# BMS-FETs.net
KiCad netlist of a schematic drawn in Altium Designer
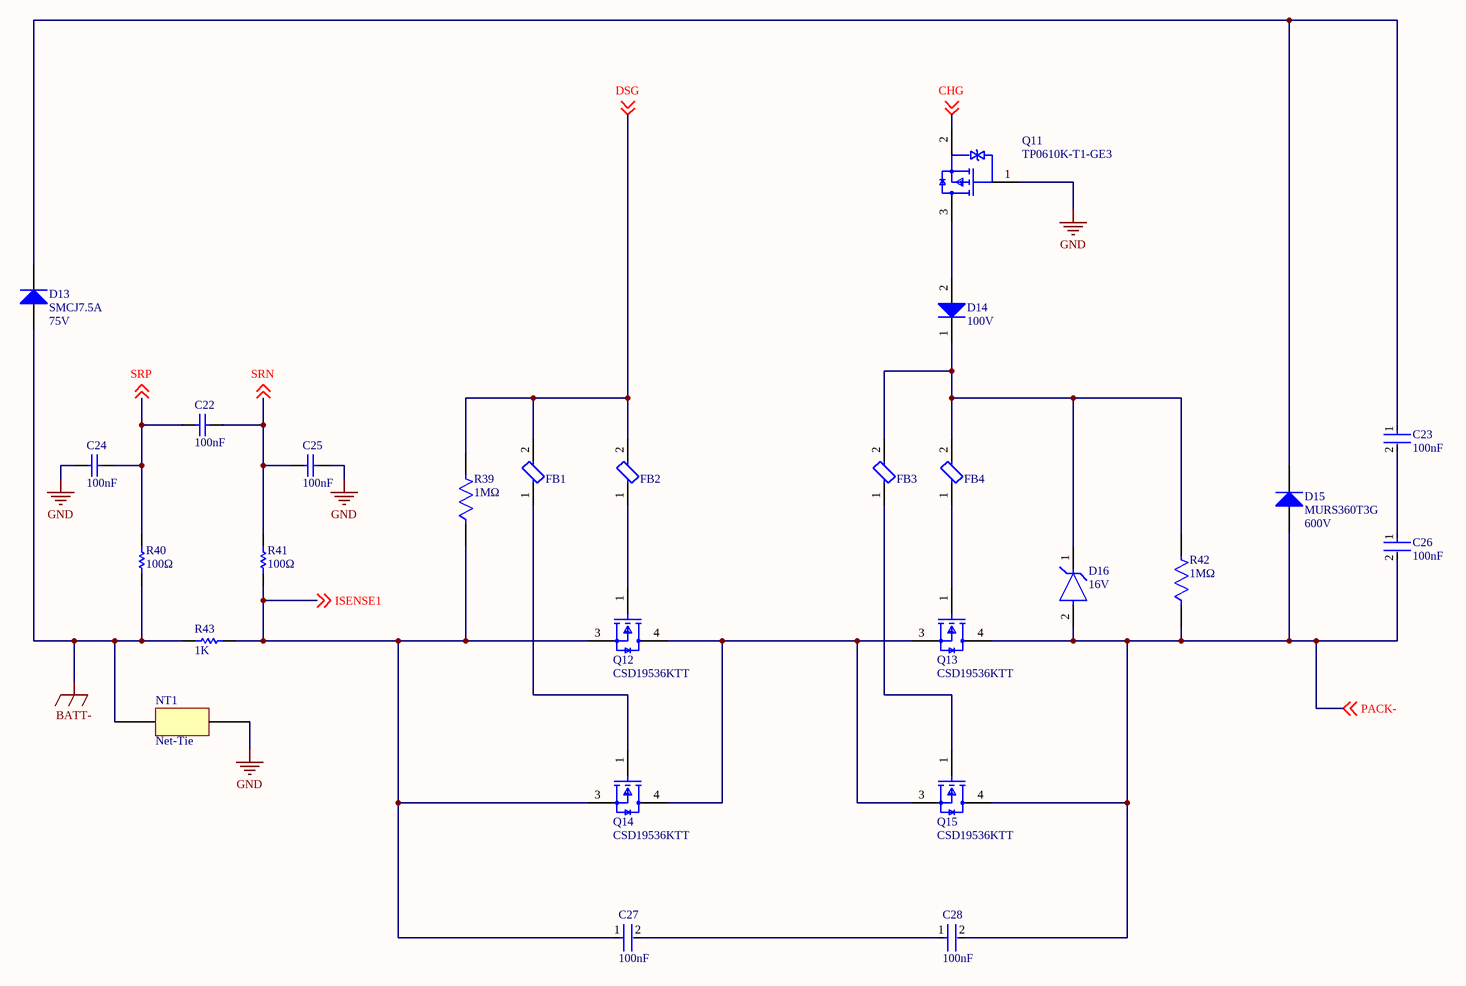
[diagram p0: BMS-FETs.SchDoc]

(export (version "E")
  (design (tool "Eeschema 10.0.6"))
  (components
    (comp (ref "C22")
      (value "885012206095")
      (footprint "WCAP-CSGP_0603_L1.6W0.8H0.8_Reflow")
      (description "CAP CER 0.1UF 50V X7R 0603")
      (fields (field (name "TOLERANCE") "10%") (field (name "CAPACITANCE") "100nF"))
      (libsource (lib "BMS-lib") (part "CMP-207839-000004-2"))
    )
    (comp (ref "C23")
      (value "GRM188R72A104KA35D")
      (footprint "FP-GRM188-0_1-e0_2_0_5-IPC_A")
      (description "Chip Multilayer Ceramic Capacitors for General Purpose, 0603, 0.10uF, X7R, 15%, 10%, 100V")
      (fields
        (field (name "VOLTAGE") "100V")
        (field (name "TOLERANCE") "10%")
        (field (name "CAPACITANCE") "100nF")
      )
      (libsource (lib "BMS-lib") (part "CMP-1035-02595-8"))
    )
    (comp (ref "C24")
      (value "885012206095")
      (footprint "WCAP-CSGP_0603_L1.6W0.8H0.8_Reflow")
      (description "CAP CER 0.1UF 50V X7R 0603")
      (fields (field (name "TOLERANCE") "10%") (field (name "CAPACITANCE") "100nF"))
      (libsource (lib "BMS-lib") (part "CMP-207839-000004-2"))
    )
    (comp (ref "C25")
      (value "885012206095")
      (footprint "WCAP-CSGP_0603_L1.6W0.8H0.8_Reflow")
      (description "CAP CER 0.1UF 50V X7R 0603")
      (fields (field (name "TOLERANCE") "10%") (field (name "CAPACITANCE") "100nF"))
      (libsource (lib "BMS-lib") (part "CMP-207839-000004-2"))
    )
    (comp (ref "C26")
      (value "GRM188R72A104KA35D")
      (footprint "FP-GRM188-0_1-e0_2_0_5-IPC_A")
      (description "Chip Multilayer Ceramic Capacitors for General Purpose, 0603, 0.10uF, X7R, 15%, 10%, 100V")
      (fields
        (field (name "VOLTAGE") "100V")
        (field (name "TOLERANCE") "10%")
        (field (name "CAPACITANCE") "100nF")
      )
      (libsource (lib "BMS-lib") (part "CMP-1035-02595-8"))
    )
    (comp (ref "C27")
      (value "GRM188R72A104KA35D")
      (footprint "FP-GRM188-0_1-e0_2_0_5-IPC_A")
      (description "Chip Multilayer Ceramic Capacitors for General Purpose, 0603, 0.10uF, X7R, 15%, 10%, 100V")
      (fields
        (field (name "VOLTAGE") "100V")
        (field (name "TOLERANCE") "10%")
        (field (name "CAPACITANCE") "100nF")
      )
      (libsource (lib "BMS-lib") (part "CMP-1035-02595-8"))
    )
    (comp (ref "C28")
      (value "GRM188R72A104KA35D")
      (footprint "FP-GRM188-0_1-e0_2_0_5-IPC_A")
      (description "Chip Multilayer Ceramic Capacitors for General Purpose, 0603, 0.10uF, X7R, 15%, 10%, 100V")
      (fields
        (field (name "VOLTAGE") "100V")
        (field (name "TOLERANCE") "10%")
        (field (name "CAPACITANCE") "100nF")
      )
      (libsource (lib "BMS-lib") (part "CMP-1035-02595-8"))
    )
    (comp (ref "D13")
      (value "SMCJ7.5A")
      (footprint "DIOM7959X262N")
      (description "Trans Voltage Suppressor Diode, 1500W, 75V V(RWM), Unidirectional, 1 Element, Silicon, DO-214AB")
      (fields (field (name "MANUFACTURER") "Littelfuse") (field (name "REP PK REVERSE VOLTAGE-MAX") "75V"))
      (libsource (lib "BMS-lib") (part "SMCJ7.5A"))
    )
    (comp (ref "D14")
      (value "MMSD914T1G")
      (footprint "ONSC-SOD-123-2-425-04_V")
      (description "Rectifier Diode, 1 Phase, 1 Element, 0.2A, 100V V(RRM), Silicon")
      (fields (field (name "MANUFACTURER") "On Semiconductor") (field (name "VOLTAGE RATING (DC)") "100V"))
      (libsource (lib "BMS-lib") (part "CMP-1054-00050-1"))
    )
    (comp (ref "D15")
      (value "MURS360T3G")
      (footprint "DIOM8059X261N")
      (description "Rectifier Diode, 1 Phase, 1 Element, 4A, 600V V(RRM), Silicon")
      (fields
        (field (name "MANUFACTURER") "ON Semiconductor")
        (field (name "REP PK REVERSE VOLTAGE-MAX") "600V")
      )
      (libsource (lib "BMS-lib") (part "MURS360T3G"))
    )
    (comp (ref "D16")
      (value "MMSZ5246B-7-F")
      (footprint "SOD3716X145N")
      (description "Zener Diode, 16V V(Z), 5%, 0.37W, Silicon, Unidirectional")
      (fields (field (name "MANUFACTURER") "Diodes") (field (name "REFERENCE VOLTAGE-NOM") "16V"))
      (libsource (lib "BMS-lib") (part "MMSZ5246B-7-F"))
    )
    (comp (ref "FB1")
      (value "BLM18SG221TN1D")
      (footprint "FP-BLM18-0_15-t0_5-IPC_C")
      (description "Chip Ferrite Bead, 0603, 220Ω @ 100MHz, 25%, 0.04Ω, 2.5A")
      (fields (field (name "TOLERANCE") "25%"))
      (libsource (lib "BMS-lib") (part "CMP-0686-00596-3"))
    )
    (comp (ref "FB2")
      (value "BLM18SG221TN1D")
      (footprint "FP-BLM18-0_15-t0_5-IPC_C")
      (description "Chip Ferrite Bead, 0603, 220Ω @ 100MHz, 25%, 0.04Ω, 2.5A")
      (fields (field (name "TOLERANCE") "25%"))
      (libsource (lib "BMS-lib") (part "CMP-0686-00596-3"))
    )
    (comp (ref "FB3")
      (value "BLM18SG221TN1D")
      (footprint "FP-BLM18-0_15-t0_5-IPC_C")
      (description "Chip Ferrite Bead, 0603, 220Ω @ 100MHz, 25%, 0.04Ω, 2.5A")
      (fields (field (name "TOLERANCE") "25%"))
      (libsource (lib "BMS-lib") (part "CMP-0686-00596-3"))
    )
    (comp (ref "FB4")
      (value "BLM18SG221TN1D")
      (footprint "FP-BLM18-0_15-t0_5-IPC_C")
      (description "Chip Ferrite Bead, 0603, 220Ω @ 100MHz, 25%, 0.04Ω, 2.5A")
      (fields (field (name "TOLERANCE") "25%"))
      (libsource (lib "BMS-lib") (part "CMP-0686-00596-3"))
    )
    (comp (ref "NT1") (value "Net-Tie") (libsource (lib "BMS-lib") (part "Net-Tie")))
    (comp (ref "Q11")
      (value "TP0610K-T1-GE3")
      (footprint "FP-S-03946-IPC_C")
      (description "MOSFET P-CH 60V 185MA SOT23-3")
      (libsource (lib "BMS-lib") (part "CMP-02550-000326-1"))
    )
    (comp (ref "Q12")
      (value "CSD19536KTT")
      (footprint "FP-CSD19536KTT-MFG")
      (description "MOSFET N-CH 100V 200A TO263")
      (fields
        (field (name "MANUFACTURER") "Texas Instruments")
        (field (name "OCTOPART") "https://octopart.com/csd19536ktt-texas+instruments-57155051")
      )
      (libsource (lib "BMS-lib") (part "CMP-04962-000010-1"))
    )
    (comp (ref "Q13")
      (value "CSD19536KTT")
      (footprint "FP-CSD19536KTT-MFG")
      (description "MOSFET N-CH 100V 200A TO263")
      (fields
        (field (name "MANUFACTURER") "Texas Instruments")
        (field (name "OCTOPART") "https://octopart.com/csd19536ktt-texas+instruments-57155051")
      )
      (libsource (lib "BMS-lib") (part "CMP-04962-000010-1"))
    )
    (comp (ref "Q14")
      (value "CSD19536KTT")
      (footprint "FP-CSD19536KTT-MFG")
      (description "MOSFET N-CH 100V 200A TO263")
      (fields
        (field (name "MANUFACTURER") "Texas Instruments")
        (field (name "OCTOPART") "https://octopart.com/csd19536ktt-texas+instruments-57155051")
      )
      (libsource (lib "BMS-lib") (part "CMP-04962-000010-1"))
    )
    (comp (ref "Q15")
      (value "CSD19536KTT")
      (footprint "FP-CSD19536KTT-MFG")
      (description "MOSFET N-CH 100V 200A TO263")
      (fields
        (field (name "MANUFACTURER") "Texas Instruments")
        (field (name "OCTOPART") "https://octopart.com/csd19536ktt-texas+instruments-57155051")
      )
      (libsource (lib "BMS-lib") (part "CMP-04962-000010-1"))
    )
    (comp (ref "R39")
      (value "CRCW06031M00FKEA")
      (footprint "FP-CRCW0603-e3-MFG")
      (description "RES Thick Film, 1MΩ, 1%, 0.1W, 100ppm/°C, 0603")
      (fields (field (name "TOLERANCE") "1%") (field (name "RESISTANCE") "1MΩ"))
      (libsource (lib "BMS-lib") (part "CMP-2000-03013-2"))
    )
    (comp (ref "R40")
      (value "CRCW0805100RFKEA")
      (footprint "RESC2013X50X30ML20T20")
      (fields (field (name "MANUFACTURER") "Vishay Dale") (field (name "RESISTANCE") "100Ω"))
      (libsource (lib "BMS-lib") (part "CMP-2001-04901-1"))
    )
    (comp (ref "R41")
      (value "CRCW0805100RFKEA")
      (footprint "RESC2013X50X30ML20T20")
      (fields (field (name "MANUFACTURER") "Vishay Dale") (field (name "RESISTANCE") "100Ω"))
      (libsource (lib "BMS-lib") (part "CMP-2001-04901-1"))
    )
    (comp (ref "R42")
      (value "CRCW06031M00FKEA")
      (footprint "FP-CRCW0603-e3-MFG")
      (description "RES Thick Film, 1MΩ, 1%, 0.1W, 100ppm/°C, 0603")
      (fields (field (name "TOLERANCE") "1%") (field (name "RESISTANCE") "1MΩ"))
      (libsource (lib "BMS-lib") (part "CMP-2000-03013-2"))
    )
    (comp (ref "R43")
      (value "1K")
      (description "Resistor")
      (libsource (lib "Simulation Generic Components") (part "Resistor"))
    )
  )
  (nets
    (net (code "1") (name "BATT-") (class "Default")
      (node (ref "D13") (pin "1") (pinfunction "A_1") (pintype "passive"))
      (node (ref "NT1") (pin "31") (pinfunction "31_31") (pintype "passive"))
      (node (ref "R40") (pin "1") (pinfunction "1_1") (pintype "passive"))
      (node (ref "R43") (pin "1") (pinfunction "1_1") (pintype "passive"))
    )
    (net (code "2") (name "CHG") (class "Default")
      (node (ref "Q11") (pin "2") (pinfunction "S_2") (pintype "passive"))
    )
    (net (code "3") (name "DSG") (class "Default")
      (node (ref "FB1") (pin "2") (pinfunction "2_2") (pintype "passive"))
      (node (ref "FB2") (pin "2") (pinfunction "2_2") (pintype "passive"))
      (node (ref "R39") (pin "2") (pinfunction "2_2") (pintype "passive"))
    )
    (net (code "4") (name "GND") (class "Default")
      (node (ref "C24") (pin "1") (pinfunction "1_1") (pintype "passive"))
      (node (ref "C25") (pin "2") (pinfunction "2_2") (pintype "passive"))
      (node (ref "NT1") (pin "32") (pinfunction "32_32") (pintype "passive"))
      (node (ref "Q11") (pin "1") (pinfunction "G_1") (pintype "passive"))
    )
    (net (code "5") (name "ISENSE1") (class "Default")
      (node (ref "C27") (pin "1") (pinfunction "1_1") (pintype "passive"))
      (node (ref "Q12") (pin "3") (pinfunction "Source_3") (pintype "passive"))
      (node (ref "Q14") (pin "3") (pinfunction "Source_3") (pintype "passive"))
      (node (ref "R39") (pin "1") (pinfunction "1_1") (pintype "passive"))
      (node (ref "R41") (pin "1") (pinfunction "1_1") (pintype "passive"))
      (node (ref "R43") (pin "2") (pinfunction "2_2") (pintype "passive"))
    )
    (net (code "6") (name "Net-(C23-Pad2)") (class "Default")
      (node (ref "C23") (pin "2") (pinfunction "2_2") (pintype "passive"))
      (node (ref "C26") (pin "1") (pinfunction "1_1") (pintype "passive"))
    )
    (net (code "7") (name "Net-(C27-Pad2)") (class "Default")
      (node (ref "C27") (pin "2") (pinfunction "2_2") (pintype "passive"))
      (node (ref "C28") (pin "1") (pinfunction "1_1") (pintype "passive"))
    )
    (net (code "8") (name "Net-(D13-K)") (class "Default")
      (node (ref "C23") (pin "1") (pinfunction "1_1") (pintype "passive"))
      (node (ref "D13") (pin "2") (pinfunction "K_2") (pintype "passive"))
      (node (ref "D15") (pin "2") (pinfunction "K_2") (pintype "passive"))
    )
    (net (code "9") (name "Net-(D14-A)") (class "Default")
      (node (ref "D14") (pin "2") (pinfunction "A_2") (pintype "passive"))
      (node (ref "Q11") (pin "3") (pinfunction "D_3") (pintype "passive"))
    )
    (net (code "10") (name "Net-(D14-K)") (class "Default")
      (node (ref "D14") (pin "1") (pinfunction "K_1") (pintype "passive"))
      (node (ref "D16") (pin "1") (pinfunction "C_1") (pintype "passive"))
      (node (ref "FB3") (pin "2") (pinfunction "2_2") (pintype "passive"))
      (node (ref "FB4") (pin "2") (pinfunction "2_2") (pintype "passive"))
      (node (ref "R42") (pin "2") (pinfunction "2_2") (pintype "passive"))
    )
    (net (code "11") (name "Net-(Q12-Drain)") (class "Default")
      (node (ref "Q12") (pin "4") (pinfunction "Drain_4") (pintype "passive"))
      (node (ref "Q13") (pin "3") (pinfunction "Source_3") (pintype "passive"))
      (node (ref "Q14") (pin "4") (pinfunction "Drain_4") (pintype "passive"))
      (node (ref "Q15") (pin "3") (pinfunction "Source_3") (pintype "passive"))
    )
    (net (code "12") (name "Net-(Q12-Gate)") (class "Default")
      (node (ref "FB2") (pin "1") (pinfunction "1_1") (pintype "passive"))
      (node (ref "Q12") (pin "1") (pinfunction "Gate_1") (pintype "passive"))
    )
    (net (code "13") (name "Net-(Q13-Gate)") (class "Default")
      (node (ref "FB4") (pin "1") (pinfunction "1_1") (pintype "passive"))
      (node (ref "Q13") (pin "1") (pinfunction "Gate_1") (pintype "passive"))
    )
    (net (code "14") (name "Net-(Q14-Gate)") (class "Default")
      (node (ref "FB1") (pin "1") (pinfunction "1_1") (pintype "passive"))
      (node (ref "Q14") (pin "1") (pinfunction "Gate_1") (pintype "passive"))
    )
    (net (code "15") (name "Net-(Q15-Gate)") (class "Default")
      (node (ref "FB3") (pin "1") (pinfunction "1_1") (pintype "passive"))
      (node (ref "Q15") (pin "1") (pinfunction "Gate_1") (pintype "passive"))
    )
    (net (code "16") (name "PACK-") (class "Default")
      (node (ref "C26") (pin "2") (pinfunction "2_2") (pintype "passive"))
      (node (ref "C28") (pin "2") (pinfunction "2_2") (pintype "passive"))
      (node (ref "D15") (pin "1") (pinfunction "A_1") (pintype "passive"))
      (node (ref "D16") (pin "2") (pinfunction "A_2") (pintype "passive"))
      (node (ref "Q13") (pin "4") (pinfunction "Drain_4") (pintype "passive"))
      (node (ref "Q15") (pin "4") (pinfunction "Drain_4") (pintype "passive"))
      (node (ref "R42") (pin "1") (pinfunction "1_1") (pintype "passive"))
    )
    (net (code "17") (name "SRN") (class "Default")
      (node (ref "C22") (pin "2") (pinfunction "2_2") (pintype "passive"))
      (node (ref "C25") (pin "1") (pinfunction "1_1") (pintype "passive"))
      (node (ref "R41") (pin "2") (pinfunction "2_2") (pintype "passive"))
    )
    (net (code "18") (name "SRP") (class "Default")
      (node (ref "C22") (pin "1") (pinfunction "1_1") (pintype "passive"))
      (node (ref "C24") (pin "2") (pinfunction "2_2") (pintype "passive"))
      (node (ref "R40") (pin "2") (pinfunction "2_2") (pintype "passive"))
    )
  )
)
